# Sheet2Viper.net
KiCad netlist of a schematic drawn in Altium Designer
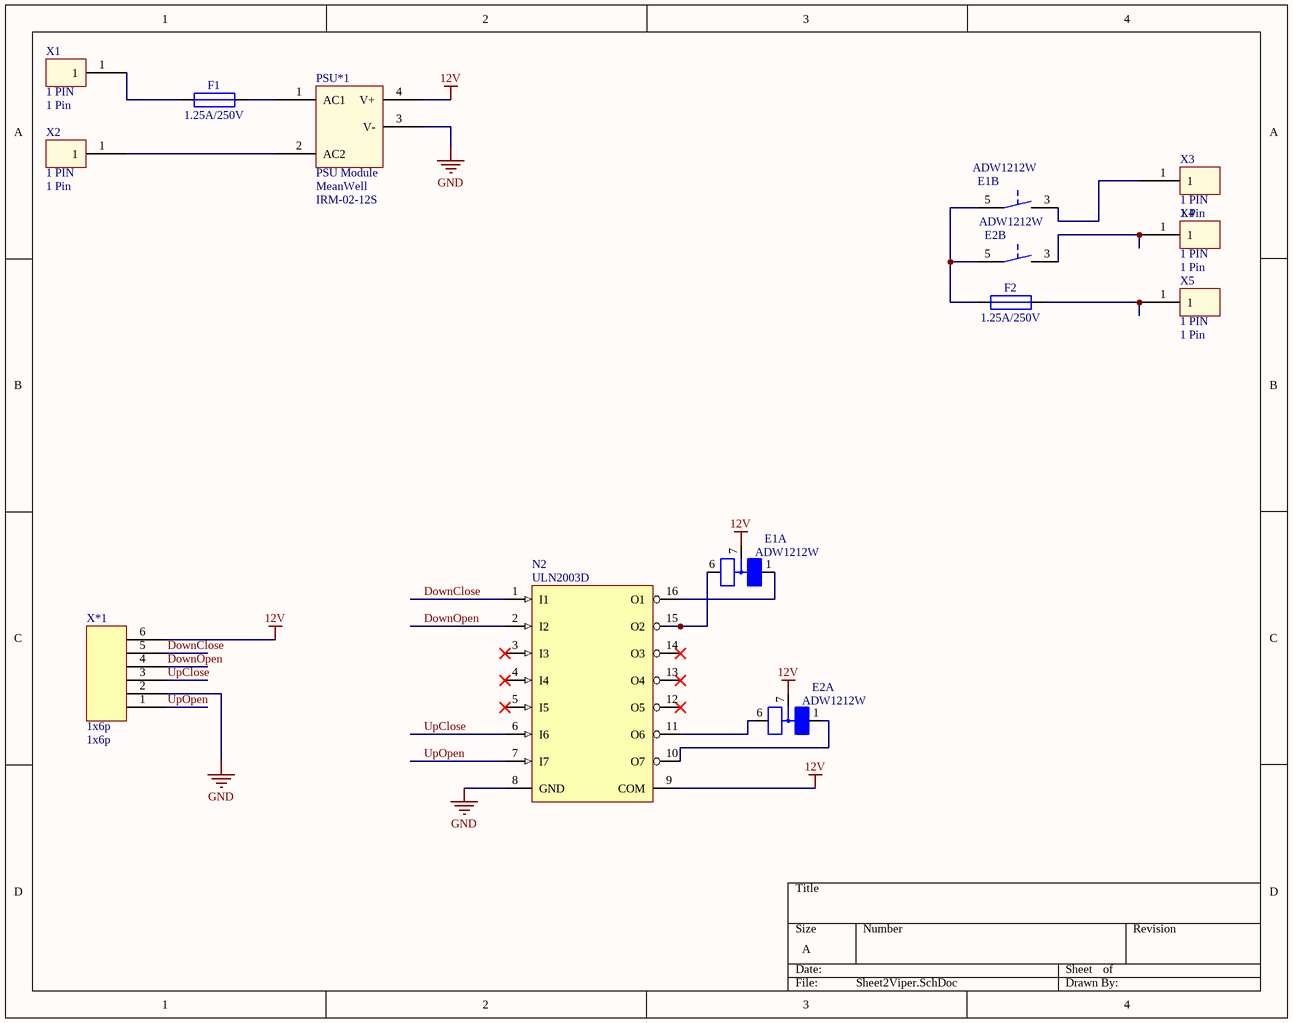
[diagram p0: Sheet2Viper.SchDoc]

(export (version "E")
  (design (tool "Eeschema 10.0.6"))
  (components
    (comp (ref "E1")
      (value "ADW1212W")
      (footprint "RELAIS_PANASONIC_ADW1212W")
      (description "04-3960 - Relais, 12V, 1S 2Coils")
      (fields (field (name "PARTNUMBER") "04-3960") (field (name "PUBLISHER") "SS"))
      (libsource (lib "") (part "ADW1212W_04-3960_1"))
    )
    (comp (ref "E2")
      (value "ADW1212W")
      (footprint "RELAIS_PANASONIC_ADW1212W")
      (description "04-3960 - Relais, 12V, 1S 2Coils")
      (fields (field (name "PARTNUMBER") "04-3960") (field (name "PUBLISHER") "SS"))
      (libsource (lib "") (part "ADW1212W_04-3960_2"))
    )
    (comp (ref "F1")
      (value "1.25A/250V")
      (footprint "FUSE_THT_8.4x4")
      (description "04-3586 - Fuse 1.25A 250V THT 8.4x4mm RM5.08mm")
      (fields (field (name "PARTNUMBER") "04-3586") (field (name "PUBLISHER") "SS"))
      (libsource (lib "AM540_rf1_1v4") (part "Fuse_1.25A_250V_04-3586"))
    )
    (comp (ref "F2")
      (value "1.25A/250V")
      (footprint "FUSE_THT_8.4x4")
      (description "04-3586 - Fuse 1.25A 250V THT 8.4x4mm RM5.08mm")
      (fields (field (name "PARTNUMBER") "04-3586") (field (name "PUBLISHER") "SS"))
      (libsource (lib "AM540_rf1_1v4") (part "Fuse_1.25A_250V_04-3586"))
    )
    (comp (ref "N2")
      (value "ULN2003D")
      (footprint "SOP127P720X175-16N")
      (description "11-0373- High-Voltage, High-Current Darlington Transistor Arrays, SOP16")
      (fields (field (name "PARTNUMBER") "11-0373") (field (name "PUBLISHER") "SS"))
      (libsource (lib "Mainboard_abc082rn1_Rev18") (part "ULN2003D_11-0373"))
    )
    (comp (ref "PSU*1")
      (value "PSU Module")
      (footprint "MeanWell Psu")
      (description "SMPS PCB Mode")
      (fields (field (name "MANUFACTURER") "MeanWell") (field (name "MANUFACTURER CODE") "IRM-02-12S"))
      (libsource (lib "Blinds") (part "PSU Module"))
    )
    (comp (ref "X*1")
      (value "1x6p")
      (footprint "1x6p")
      (fields (field (name "MANUFACTURER") "TI") (field (name "MANUFACTURER CODE") "1x6p"))
      (libsource (lib "Blinds") (part "1x6p"))
    )
    (comp (ref "X1")
      (value "1 PIN")
      (footprint "1p")
      (fields (field (name "1") "1 Pin"))
      (libsource (lib "") (part "1 PIN_1"))
    )
    (comp (ref "X2")
      (value "1 PIN")
      (footprint "1p")
      (fields (field (name "1") "1 Pin"))
      (libsource (lib "") (part "1 PIN_1"))
    )
    (comp (ref "X3")
      (value "1 PIN")
      (footprint "1p")
      (fields (field (name "1") "1 Pin"))
      (libsource (lib "Blinds") (part "1 PIN"))
    )
    (comp (ref "X4")
      (value "1 PIN")
      (footprint "1p")
      (fields (field (name "1") "1 Pin"))
      (libsource (lib "Blinds") (part "1 PIN"))
    )
    (comp (ref "X5")
      (value "1 PIN")
      (footprint "1p")
      (fields (field (name "1") "1 Pin"))
      (libsource (lib "Blinds") (part "1 PIN"))
    )
  )
  (nets
    (net (code "1") (name "/DownClose") (class "Default")
      (node (ref "N2") (pin "1") (pinfunction "I1_1") (pintype "input"))
      (node (ref "X*1") (pin "5") (pintype "passive"))
    )
    (net (code "2") (name "/DownOpen") (class "Default")
      (node (ref "N2") (pin "2") (pinfunction "I2_2") (pintype "input"))
      (node (ref "X*1") (pin "4") (pintype "passive"))
    )
    (net (code "3") (name "/UpClose") (class "Default")
      (node (ref "N2") (pin "6") (pinfunction "I6_6") (pintype "input"))
      (node (ref "X*1") (pin "3") (pintype "passive"))
    )
    (net (code "4") (name "/UpOpen") (class "Default")
      (node (ref "N2") (pin "7") (pinfunction "I7_7") (pintype "input"))
      (node (ref "X*1") (pin "1") (pintype "passive"))
    )
    (net (code "5") (name "12V") (class "Default")
      (node (ref "E1") (pin "7") (pinfunction "P_7") (pintype "passive"))
      (node (ref "E2") (pin "7") (pinfunction "P_7") (pintype "passive"))
      (node (ref "N2") (pin "9") (pinfunction "COM_9") (pintype "passive"))
      (node (ref "PSU*1") (pin "4") (pinfunction "V+_4") (pintype "passive"))
      (node (ref "X*1") (pin "6") (pintype "passive"))
    )
    (net (code "6") (name "GND") (class "Default")
      (node (ref "N2") (pin "8") (pinfunction "GND_8") (pintype "power_in"))
      (node (ref "PSU*1") (pin "3") (pinfunction "V-_3") (pintype "passive"))
      (node (ref "X*1") (pin "2") (pintype "passive"))
    )
    (net (code "7") (name "Net-(E1-Pad3)") (class "Default")
      (node (ref "E1") (pin "3") (pinfunction "3_3") (pintype "passive"))
      (node (ref "X3") (pin "1") (pinfunction "1_1") (pintype "passive"))
    )
    (net (code "8") (name "Net-(E1-Pad5)") (class "Default")
      (node (ref "E1") (pin "5") (pinfunction "5_5") (pintype "passive"))
      (node (ref "E2") (pin "5") (pinfunction "5_5") (pintype "passive"))
      (node (ref "F2") (pin "1") (pinfunction "1_1") (pintype "passive"))
    )
    (net (code "9") (name "Net-(E1A-M)") (class "Default")
      (node (ref "E1") (pin "1") (pinfunction "M_1") (pintype "passive"))
      (node (ref "N2") (pin "16") (pinfunction "O1_16") (pintype "passive"))
    )
    (net (code "10") (name "Net-(E1A-M1)") (class "Default")
      (node (ref "E1") (pin "6") (pinfunction "M1_6") (pintype "passive"))
      (node (ref "N2") (pin "15") (pinfunction "O2_15") (pintype "passive"))
    )
    (net (code "11") (name "Net-(E2-Pad3)") (class "Default")
      (node (ref "E2") (pin "3") (pinfunction "3_3") (pintype "passive"))
      (node (ref "X4") (pin "1") (pinfunction "1_1") (pintype "passive"))
    )
    (net (code "12") (name "Net-(E2A-M)") (class "Default")
      (node (ref "E2") (pin "1") (pinfunction "M_1") (pintype "passive"))
      (node (ref "N2") (pin "10") (pinfunction "O7_10") (pintype "passive"))
    )
    (net (code "13") (name "Net-(E2A-M1)") (class "Default")
      (node (ref "E2") (pin "6") (pinfunction "M1_6") (pintype "passive"))
      (node (ref "N2") (pin "11") (pinfunction "O6_11") (pintype "passive"))
    )
    (net (code "14") (name "Net-(F1-Pad1)") (class "Default")
      (node (ref "F1") (pin "1") (pinfunction "1_1") (pintype "passive"))
      (node (ref "X1") (pin "1") (pinfunction "1_1") (pintype "passive"))
    )
    (net (code "15") (name "Net-(F2-Pad2)") (class "Default")
      (node (ref "F2") (pin "2") (pinfunction "2_2") (pintype "passive"))
      (node (ref "X5") (pin "1") (pinfunction "1_1") (pintype "passive"))
    )
    (net (code "16") (name "Net-(PSU*1-AC1)") (class "Default")
      (node (ref "F1") (pin "2") (pinfunction "2_2") (pintype "passive"))
      (node (ref "PSU*1") (pin "1") (pinfunction "AC1_1") (pintype "passive"))
    )
    (net (code "17") (name "Net-(PSU*1-AC2)") (class "Default")
      (node (ref "PSU*1") (pin "2") (pinfunction "AC2_2") (pintype "passive"))
      (node (ref "X2") (pin "1") (pinfunction "1_1") (pintype "passive"))
    )
    (net (code "18") (name "unconnected-(N2-I3-Pad3)") (class "Default")
      (node (ref "N2") (pin "3") (pinfunction "I3_3") (pintype "input+no_connect"))
    )
    (net (code "19") (name "unconnected-(N2-I4-Pad4)") (class "Default")
      (node (ref "N2") (pin "4") (pinfunction "I4_4") (pintype "input+no_connect"))
    )
    (net (code "20") (name "unconnected-(N2-I5-Pad5)") (class "Default")
      (node (ref "N2") (pin "5") (pinfunction "I5_5") (pintype "input+no_connect"))
    )
    (net (code "21") (name "unconnected-(N2-O3-Pad14)") (class "Default")
      (node (ref "N2") (pin "14") (pinfunction "O3_14") (pintype "passive+no_connect"))
    )
    (net (code "22") (name "unconnected-(N2-O4-Pad13)") (class "Default")
      (node (ref "N2") (pin "13") (pinfunction "O4_13") (pintype "passive+no_connect"))
    )
    (net (code "23") (name "unconnected-(N2-O5-Pad12)") (class "Default")
      (node (ref "N2") (pin "12") (pinfunction "O5_12") (pintype "passive+no_connect"))
    )
  )
)
